# motor_driver.net
KiCad netlist of a schematic drawn in EAGLE
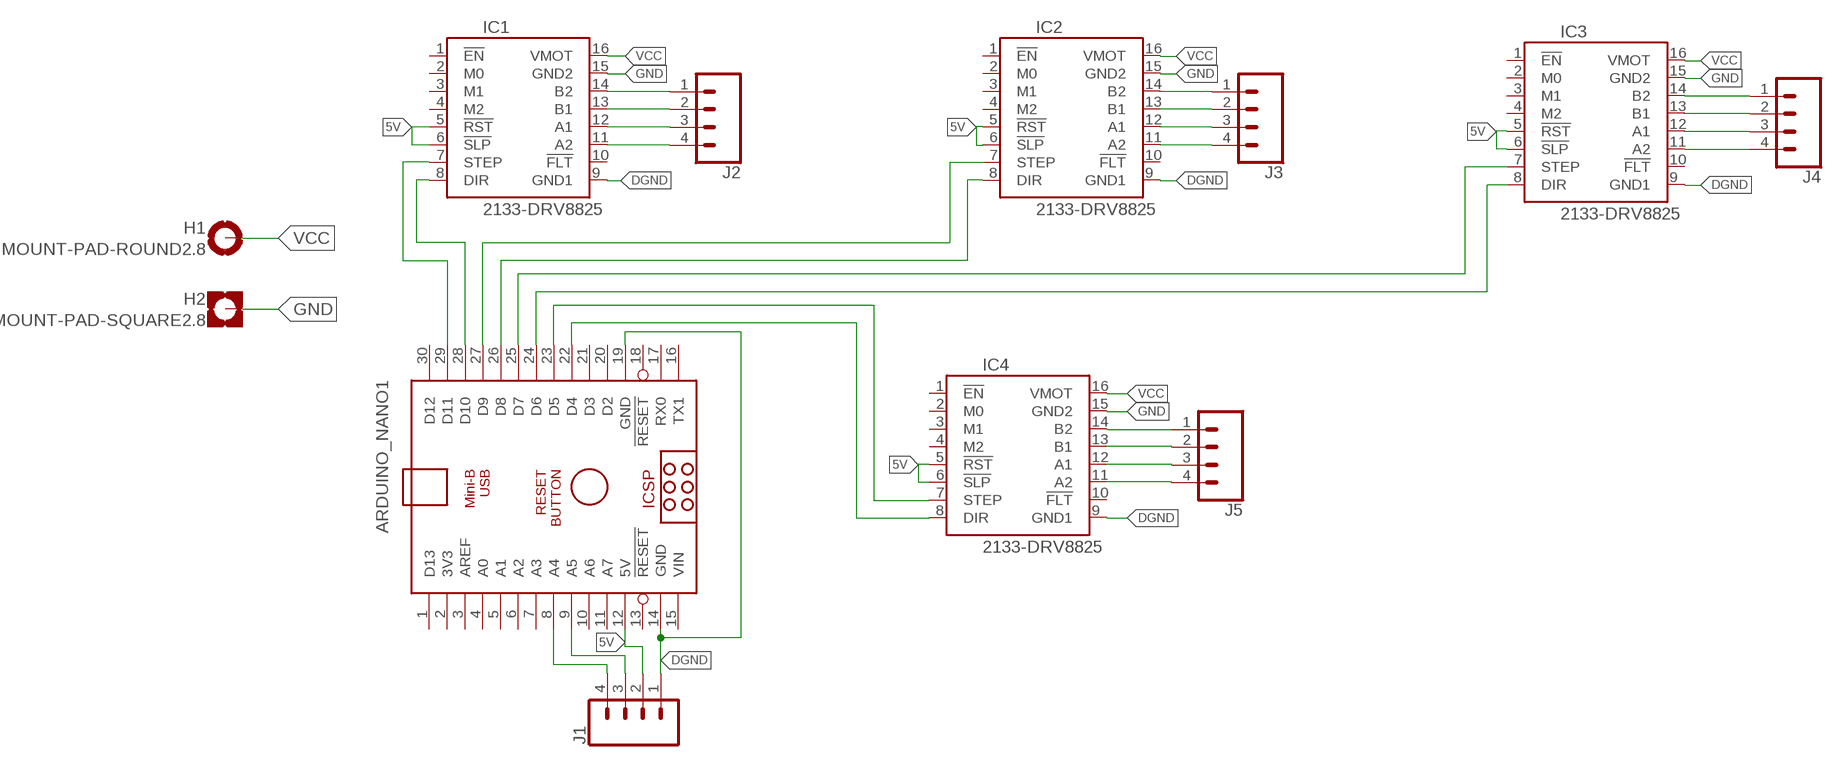
[diagram p0: schematic, sheet 1]

(export (version "E")
  (design (tool "Eeschema 10.0.6"))
  (components
    (comp (ref "ARDUINO_NANO1")
      (value "ARDUINO_NANO")
      (footprint "eagle-import:ARDUINO_NANO")
      (libsource (lib "eagle-import") (part "ARDUINO_NANO"))
    )
    (comp (ref "H1")
      (value "MOUNT-PAD-ROUND2.8")
      (footprint "eagle-import:2,8-PAD")
      (libsource (lib "eagle-import") (part "MOUNT-PAD-ROUND2.8"))
    )
    (comp (ref "H2")
      (value "MOUNT-PAD-SQUARE2.8")
      (footprint "eagle-import:2,8-PAD-SQUARE")
      (libsource (lib "eagle-import") (part "MOUNT-PAD-SQUARE2.8"))
    )
    (comp (ref "IC1")
      (value "2133-DRV8825")
      (footprint "eagle-import:DRV8825")
      (libsource (lib "eagle-import") (part "2133-DRV8825"))
    )
    (comp (ref "IC2")
      (value "2133-DRV8825")
      (footprint "eagle-import:DRV8825")
      (libsource (lib "eagle-import") (part "2133-DRV8825"))
    )
    (comp (ref "IC3")
      (value "2133-DRV8825")
      (footprint "eagle-import:DRV8825")
      (libsource (lib "eagle-import") (part "2133-DRV8825"))
    )
    (comp (ref "IC4")
      (value "2133-DRV8825")
      (footprint "eagle-import:DRV8825")
      (libsource (lib "eagle-import") (part "2133-DRV8825"))
    )
    (comp (ref "J1")
      (value "CONN_04")
      (footprint "eagle-import:1X04")
      (libsource (lib "eagle-import") (part "CONN_04"))
    )
    (comp (ref "J2")
      (value "CONN_04")
      (footprint "eagle-import:1X04")
      (libsource (lib "eagle-import") (part "CONN_04"))
    )
    (comp (ref "J3")
      (value "CONN_04")
      (footprint "eagle-import:1X04")
      (libsource (lib "eagle-import") (part "CONN_04"))
    )
    (comp (ref "J4")
      (value "CONN_04")
      (footprint "eagle-import:1X04")
      (libsource (lib "eagle-import") (part "CONN_04"))
    )
    (comp (ref "J5")
      (value "CONN_04")
      (footprint "eagle-import:1X04")
      (libsource (lib "eagle-import") (part "CONN_04"))
    )
  )
  (nets
    (net (code "1") (name "/VIN") (class "Default")
      (node (ref "ARDUINO_NANO1") (pin "15") (pinfunction "VIN_15") (pintype "power_in"))
    )
    (net (code "2") (name "5V") (class "Default")
      (node (ref "ARDUINO_NANO1") (pin "12") (pinfunction "5V_12") (pintype "power_in"))
      (node (ref "IC1") (pin "5") (pinfunction "~{RST}_5") (pintype "input"))
      (node (ref "IC1") (pin "6") (pinfunction "~{SLP}_6") (pintype "input"))
      (node (ref "IC2") (pin "5") (pinfunction "~{RST}_5") (pintype "input"))
      (node (ref "IC2") (pin "6") (pinfunction "~{SLP}_6") (pintype "input"))
      (node (ref "IC3") (pin "5") (pinfunction "~{RST}_5") (pintype "input"))
      (node (ref "IC3") (pin "6") (pinfunction "~{SLP}_6") (pintype "input"))
      (node (ref "IC4") (pin "5") (pinfunction "~{RST}_5") (pintype "input"))
      (node (ref "IC4") (pin "6") (pinfunction "~{SLP}_6") (pintype "input"))
      (node (ref "J1") (pin "2") (pinfunction "2_2") (pintype "passive"))
    )
    (net (code "3") (name "DGND") (class "Default")
      (node (ref "ARDUINO_NANO1") (pin "14") (pinfunction "GND_14") (pintype "power_in"))
      (node (ref "ARDUINO_NANO1") (pin "19") (pinfunction "GND_19") (pintype "power_in"))
      (node (ref "IC1") (pin "9") (pinfunction "GND1_9") (pintype "power_in"))
      (node (ref "IC2") (pin "9") (pinfunction "GND1_9") (pintype "power_in"))
      (node (ref "IC3") (pin "9") (pinfunction "GND1_9") (pintype "power_in"))
      (node (ref "IC4") (pin "9") (pinfunction "GND1_9") (pintype "power_in"))
      (node (ref "J1") (pin "1") (pinfunction "1_1") (pintype "passive"))
    )
    (net (code "4") (name "GND") (class "Default")
      (node (ref "H2") (pin "B2,8") (pinfunction "MOUNT_B2,8") (pintype "passive"))
      (node (ref "IC1") (pin "15") (pinfunction "GND2_15") (pintype "power_in"))
      (node (ref "IC2") (pin "15") (pinfunction "GND2_15") (pintype "power_in"))
      (node (ref "IC3") (pin "15") (pinfunction "GND2_15") (pintype "power_in"))
      (node (ref "IC4") (pin "15") (pinfunction "GND2_15") (pintype "power_in"))
    )
    (net (code "5") (name "Net-(ARDUINO_NANO1-A4)") (class "Default")
      (node (ref "ARDUINO_NANO1") (pin "8") (pinfunction "A4_8") (pintype "bidirectional"))
      (node (ref "J1") (pin "4") (pinfunction "4_4") (pintype "passive"))
    )
    (net (code "6") (name "Net-(ARDUINO_NANO1-A5)") (class "Default")
      (node (ref "ARDUINO_NANO1") (pin "9") (pinfunction "A5_9") (pintype "bidirectional"))
      (node (ref "J1") (pin "3") (pinfunction "3_3") (pintype "passive"))
    )
    (net (code "7") (name "Net-(ARDUINO_NANO1-D4)") (class "Default")
      (node (ref "ARDUINO_NANO1") (pin "22") (pinfunction "D4_22") (pintype "bidirectional"))
      (node (ref "IC4") (pin "8") (pinfunction "DIR_8") (pintype "input"))
    )
    (net (code "8") (name "Net-(ARDUINO_NANO1-D5)") (class "Default")
      (node (ref "ARDUINO_NANO1") (pin "23") (pinfunction "D5_23") (pintype "bidirectional"))
      (node (ref "IC4") (pin "7") (pinfunction "STEP_7") (pintype "input"))
    )
    (net (code "9") (name "Net-(ARDUINO_NANO1-D6)") (class "Default")
      (node (ref "ARDUINO_NANO1") (pin "24") (pinfunction "D6_24") (pintype "bidirectional"))
      (node (ref "IC3") (pin "8") (pinfunction "DIR_8") (pintype "input"))
    )
    (net (code "10") (name "Net-(ARDUINO_NANO1-D7)") (class "Default")
      (node (ref "ARDUINO_NANO1") (pin "25") (pinfunction "D7_25") (pintype "bidirectional"))
      (node (ref "IC3") (pin "7") (pinfunction "STEP_7") (pintype "input"))
    )
    (net (code "11") (name "Net-(ARDUINO_NANO1-D8)") (class "Default")
      (node (ref "ARDUINO_NANO1") (pin "26") (pinfunction "D8_26") (pintype "bidirectional"))
      (node (ref "IC2") (pin "8") (pinfunction "DIR_8") (pintype "input"))
    )
    (net (code "12") (name "Net-(ARDUINO_NANO1-D9)") (class "Default")
      (node (ref "ARDUINO_NANO1") (pin "27") (pinfunction "D9_27") (pintype "bidirectional"))
      (node (ref "IC2") (pin "7") (pinfunction "STEP_7") (pintype "input"))
    )
    (net (code "13") (name "Net-(ARDUINO_NANO1-D10)") (class "Default")
      (node (ref "ARDUINO_NANO1") (pin "28") (pinfunction "D10_28") (pintype "bidirectional"))
      (node (ref "IC1") (pin "8") (pinfunction "DIR_8") (pintype "input"))
    )
    (net (code "14") (name "Net-(ARDUINO_NANO1-D11)") (class "Default")
      (node (ref "ARDUINO_NANO1") (pin "29") (pinfunction "D11_29") (pintype "bidirectional"))
      (node (ref "IC1") (pin "7") (pinfunction "STEP_7") (pintype "input"))
    )
    (net (code "15") (name "Net-(IC1-A1)") (class "Default")
      (node (ref "IC1") (pin "12") (pinfunction "A1_12") (pintype "output"))
      (node (ref "J2") (pin "3") (pinfunction "3_3") (pintype "passive"))
    )
    (net (code "16") (name "Net-(IC1-A2)") (class "Default")
      (node (ref "IC1") (pin "11") (pinfunction "A2_11") (pintype "output"))
      (node (ref "J2") (pin "4") (pinfunction "4_4") (pintype "passive"))
    )
    (net (code "17") (name "Net-(IC1-B1)") (class "Default")
      (node (ref "IC1") (pin "13") (pinfunction "B1_13") (pintype "output"))
      (node (ref "J2") (pin "2") (pinfunction "2_2") (pintype "passive"))
    )
    (net (code "18") (name "Net-(IC1-B2)") (class "Default")
      (node (ref "IC1") (pin "14") (pinfunction "B2_14") (pintype "output"))
      (node (ref "J2") (pin "1") (pinfunction "1_1") (pintype "passive"))
    )
    (net (code "19") (name "Net-(IC2-A1)") (class "Default")
      (node (ref "IC2") (pin "12") (pinfunction "A1_12") (pintype "output"))
      (node (ref "J3") (pin "3") (pinfunction "3_3") (pintype "passive"))
    )
    (net (code "20") (name "Net-(IC2-A2)") (class "Default")
      (node (ref "IC2") (pin "11") (pinfunction "A2_11") (pintype "output"))
      (node (ref "J3") (pin "4") (pinfunction "4_4") (pintype "passive"))
    )
    (net (code "21") (name "Net-(IC2-B1)") (class "Default")
      (node (ref "IC2") (pin "13") (pinfunction "B1_13") (pintype "output"))
      (node (ref "J3") (pin "2") (pinfunction "2_2") (pintype "passive"))
    )
    (net (code "22") (name "Net-(IC2-B2)") (class "Default")
      (node (ref "IC2") (pin "14") (pinfunction "B2_14") (pintype "output"))
      (node (ref "J3") (pin "1") (pinfunction "1_1") (pintype "passive"))
    )
    (net (code "23") (name "Net-(IC3-A1)") (class "Default")
      (node (ref "IC3") (pin "12") (pinfunction "A1_12") (pintype "output"))
      (node (ref "J4") (pin "3") (pinfunction "3_3") (pintype "passive"))
    )
    (net (code "24") (name "Net-(IC3-A2)") (class "Default")
      (node (ref "IC3") (pin "11") (pinfunction "A2_11") (pintype "output"))
      (node (ref "J4") (pin "4") (pinfunction "4_4") (pintype "passive"))
    )
    (net (code "25") (name "Net-(IC3-B1)") (class "Default")
      (node (ref "IC3") (pin "13") (pinfunction "B1_13") (pintype "output"))
      (node (ref "J4") (pin "2") (pinfunction "2_2") (pintype "passive"))
    )
    (net (code "26") (name "Net-(IC3-B2)") (class "Default")
      (node (ref "IC3") (pin "14") (pinfunction "B2_14") (pintype "output"))
      (node (ref "J4") (pin "1") (pinfunction "1_1") (pintype "passive"))
    )
    (net (code "27") (name "Net-(IC4-A1)") (class "Default")
      (node (ref "IC4") (pin "12") (pinfunction "A1_12") (pintype "output"))
      (node (ref "J5") (pin "3") (pinfunction "3_3") (pintype "passive"))
    )
    (net (code "28") (name "Net-(IC4-A2)") (class "Default")
      (node (ref "IC4") (pin "11") (pinfunction "A2_11") (pintype "output"))
      (node (ref "J5") (pin "4") (pinfunction "4_4") (pintype "passive"))
    )
    (net (code "29") (name "Net-(IC4-B1)") (class "Default")
      (node (ref "IC4") (pin "13") (pinfunction "B1_13") (pintype "output"))
      (node (ref "J5") (pin "2") (pinfunction "2_2") (pintype "passive"))
    )
    (net (code "30") (name "Net-(IC4-B2)") (class "Default")
      (node (ref "IC4") (pin "14") (pinfunction "B2_14") (pintype "output"))
      (node (ref "J5") (pin "1") (pinfunction "1_1") (pintype "passive"))
    )
    (net (code "31") (name "VCC") (class "Default")
      (node (ref "H1") (pin "B2,8") (pinfunction "MOUNT_B2,8") (pintype "passive"))
      (node (ref "IC1") (pin "16") (pinfunction "VMOT_16") (pintype "power_in"))
      (node (ref "IC2") (pin "16") (pinfunction "VMOT_16") (pintype "power_in"))
      (node (ref "IC3") (pin "16") (pinfunction "VMOT_16") (pintype "power_in"))
      (node (ref "IC4") (pin "16") (pinfunction "VMOT_16") (pintype "power_in"))
    )
    (net (code "32") (name "unconnected-(ARDUINO_NANO1-3V3-Pad2)") (class "Default")
      (node (ref "ARDUINO_NANO1") (pin "2") (pinfunction "3V3_2") (pintype "output"))
    )
    (net (code "33") (name "unconnected-(ARDUINO_NANO1-A0-Pad4)") (class "Default")
      (node (ref "ARDUINO_NANO1") (pin "4") (pinfunction "A0_4") (pintype "bidirectional"))
    )
    (net (code "34") (name "unconnected-(ARDUINO_NANO1-A1-Pad5)") (class "Default")
      (node (ref "ARDUINO_NANO1") (pin "5") (pinfunction "A1_5") (pintype "bidirectional"))
    )
    (net (code "35") (name "unconnected-(ARDUINO_NANO1-A2-Pad6)") (class "Default")
      (node (ref "ARDUINO_NANO1") (pin "6") (pinfunction "A2_6") (pintype "bidirectional"))
    )
    (net (code "36") (name "unconnected-(ARDUINO_NANO1-A3-Pad7)") (class "Default")
      (node (ref "ARDUINO_NANO1") (pin "7") (pinfunction "A3_7") (pintype "bidirectional"))
    )
    (net (code "37") (name "unconnected-(ARDUINO_NANO1-A6-Pad10)") (class "Default")
      (node (ref "ARDUINO_NANO1") (pin "10") (pinfunction "A6_10") (pintype "bidirectional"))
    )
    (net (code "38") (name "unconnected-(ARDUINO_NANO1-A7-Pad11)") (class "Default")
      (node (ref "ARDUINO_NANO1") (pin "11") (pinfunction "A7_11") (pintype "bidirectional"))
    )
    (net (code "39") (name "unconnected-(ARDUINO_NANO1-AREF-Pad3)") (class "Default")
      (node (ref "ARDUINO_NANO1") (pin "3") (pinfunction "AREF_3") (pintype "input"))
    )
    (net (code "40") (name "unconnected-(ARDUINO_NANO1-D2-Pad20)") (class "Default")
      (node (ref "ARDUINO_NANO1") (pin "20") (pinfunction "D2_20") (pintype "bidirectional"))
    )
    (net (code "41") (name "unconnected-(ARDUINO_NANO1-D3-Pad21)") (class "Default")
      (node (ref "ARDUINO_NANO1") (pin "21") (pinfunction "D3_21") (pintype "bidirectional"))
    )
    (net (code "42") (name "unconnected-(ARDUINO_NANO1-D12-Pad30)") (class "Default")
      (node (ref "ARDUINO_NANO1") (pin "30") (pinfunction "D12_30") (pintype "bidirectional"))
    )
    (net (code "43") (name "unconnected-(ARDUINO_NANO1-D13-Pad1)") (class "Default")
      (node (ref "ARDUINO_NANO1") (pin "1") (pinfunction "D13_1") (pintype "bidirectional"))
    )
    (net (code "44") (name "unconnected-(ARDUINO_NANO1-RX0-Pad17)") (class "Default")
      (node (ref "ARDUINO_NANO1") (pin "17") (pinfunction "RX0_17") (pintype "bidirectional"))
    )
    (net (code "45") (name "unconnected-(ARDUINO_NANO1-TX1-Pad16)") (class "Default")
      (node (ref "ARDUINO_NANO1") (pin "16") (pinfunction "TX1_16") (pintype "bidirectional"))
    )
    (net (code "46") (name "unconnected-(ARDUINO_NANO1-~{RESET}-Pad13)") (class "Default")
      (node (ref "ARDUINO_NANO1") (pin "13") (pinfunction "~{RESET}_13") (pintype "input"))
    )
    (net (code "47") (name "unconnected-(ARDUINO_NANO1-~{RESET}-Pad18)") (class "Default")
      (node (ref "ARDUINO_NANO1") (pin "18") (pinfunction "~{RESET}_18") (pintype "input"))
    )
    (net (code "48") (name "unconnected-(IC1-M0-Pad2)") (class "Default")
      (node (ref "IC1") (pin "2") (pinfunction "M0_2") (pintype "passive"))
    )
    (net (code "49") (name "unconnected-(IC1-M1-Pad3)") (class "Default")
      (node (ref "IC1") (pin "3") (pinfunction "M1_3") (pintype "passive"))
    )
    (net (code "50") (name "unconnected-(IC1-M2-Pad4)") (class "Default")
      (node (ref "IC1") (pin "4") (pinfunction "M2_4") (pintype "passive"))
    )
    (net (code "51") (name "unconnected-(IC1-~{EN}-Pad1)") (class "Default")
      (node (ref "IC1") (pin "1") (pinfunction "~{EN}_1") (pintype "passive"))
    )
    (net (code "52") (name "unconnected-(IC1-~{FLT}-Pad10)") (class "Default")
      (node (ref "IC1") (pin "10") (pinfunction "~{FLT}_10") (pintype "open_collector"))
    )
    (net (code "53") (name "unconnected-(IC2-M0-Pad2)") (class "Default")
      (node (ref "IC2") (pin "2") (pinfunction "M0_2") (pintype "passive"))
    )
    (net (code "54") (name "unconnected-(IC2-M1-Pad3)") (class "Default")
      (node (ref "IC2") (pin "3") (pinfunction "M1_3") (pintype "passive"))
    )
    (net (code "55") (name "unconnected-(IC2-M2-Pad4)") (class "Default")
      (node (ref "IC2") (pin "4") (pinfunction "M2_4") (pintype "passive"))
    )
    (net (code "56") (name "unconnected-(IC2-~{EN}-Pad1)") (class "Default")
      (node (ref "IC2") (pin "1") (pinfunction "~{EN}_1") (pintype "passive"))
    )
    (net (code "57") (name "unconnected-(IC2-~{FLT}-Pad10)") (class "Default")
      (node (ref "IC2") (pin "10") (pinfunction "~{FLT}_10") (pintype "open_collector"))
    )
    (net (code "58") (name "unconnected-(IC3-M0-Pad2)") (class "Default")
      (node (ref "IC3") (pin "2") (pinfunction "M0_2") (pintype "passive"))
    )
    (net (code "59") (name "unconnected-(IC3-M1-Pad3)") (class "Default")
      (node (ref "IC3") (pin "3") (pinfunction "M1_3") (pintype "passive"))
    )
    (net (code "60") (name "unconnected-(IC3-M2-Pad4)") (class "Default")
      (node (ref "IC3") (pin "4") (pinfunction "M2_4") (pintype "passive"))
    )
    (net (code "61") (name "unconnected-(IC3-~{EN}-Pad1)") (class "Default")
      (node (ref "IC3") (pin "1") (pinfunction "~{EN}_1") (pintype "passive"))
    )
    (net (code "62") (name "unconnected-(IC3-~{FLT}-Pad10)") (class "Default")
      (node (ref "IC3") (pin "10") (pinfunction "~{FLT}_10") (pintype "open_collector"))
    )
    (net (code "63") (name "unconnected-(IC4-M0-Pad2)") (class "Default")
      (node (ref "IC4") (pin "2") (pinfunction "M0_2") (pintype "passive"))
    )
    (net (code "64") (name "unconnected-(IC4-M1-Pad3)") (class "Default")
      (node (ref "IC4") (pin "3") (pinfunction "M1_3") (pintype "passive"))
    )
    (net (code "65") (name "unconnected-(IC4-M2-Pad4)") (class "Default")
      (node (ref "IC4") (pin "4") (pinfunction "M2_4") (pintype "passive"))
    )
    (net (code "66") (name "unconnected-(IC4-~{EN}-Pad1)") (class "Default")
      (node (ref "IC4") (pin "1") (pinfunction "~{EN}_1") (pintype "passive"))
    )
    (net (code "67") (name "unconnected-(IC4-~{FLT}-Pad10)") (class "Default")
      (node (ref "IC4") (pin "10") (pinfunction "~{FLT}_10") (pintype "open_collector"))
    )
  )
)
